# Module02.net
KiCad netlist of a schematic drawn in Altium Designer
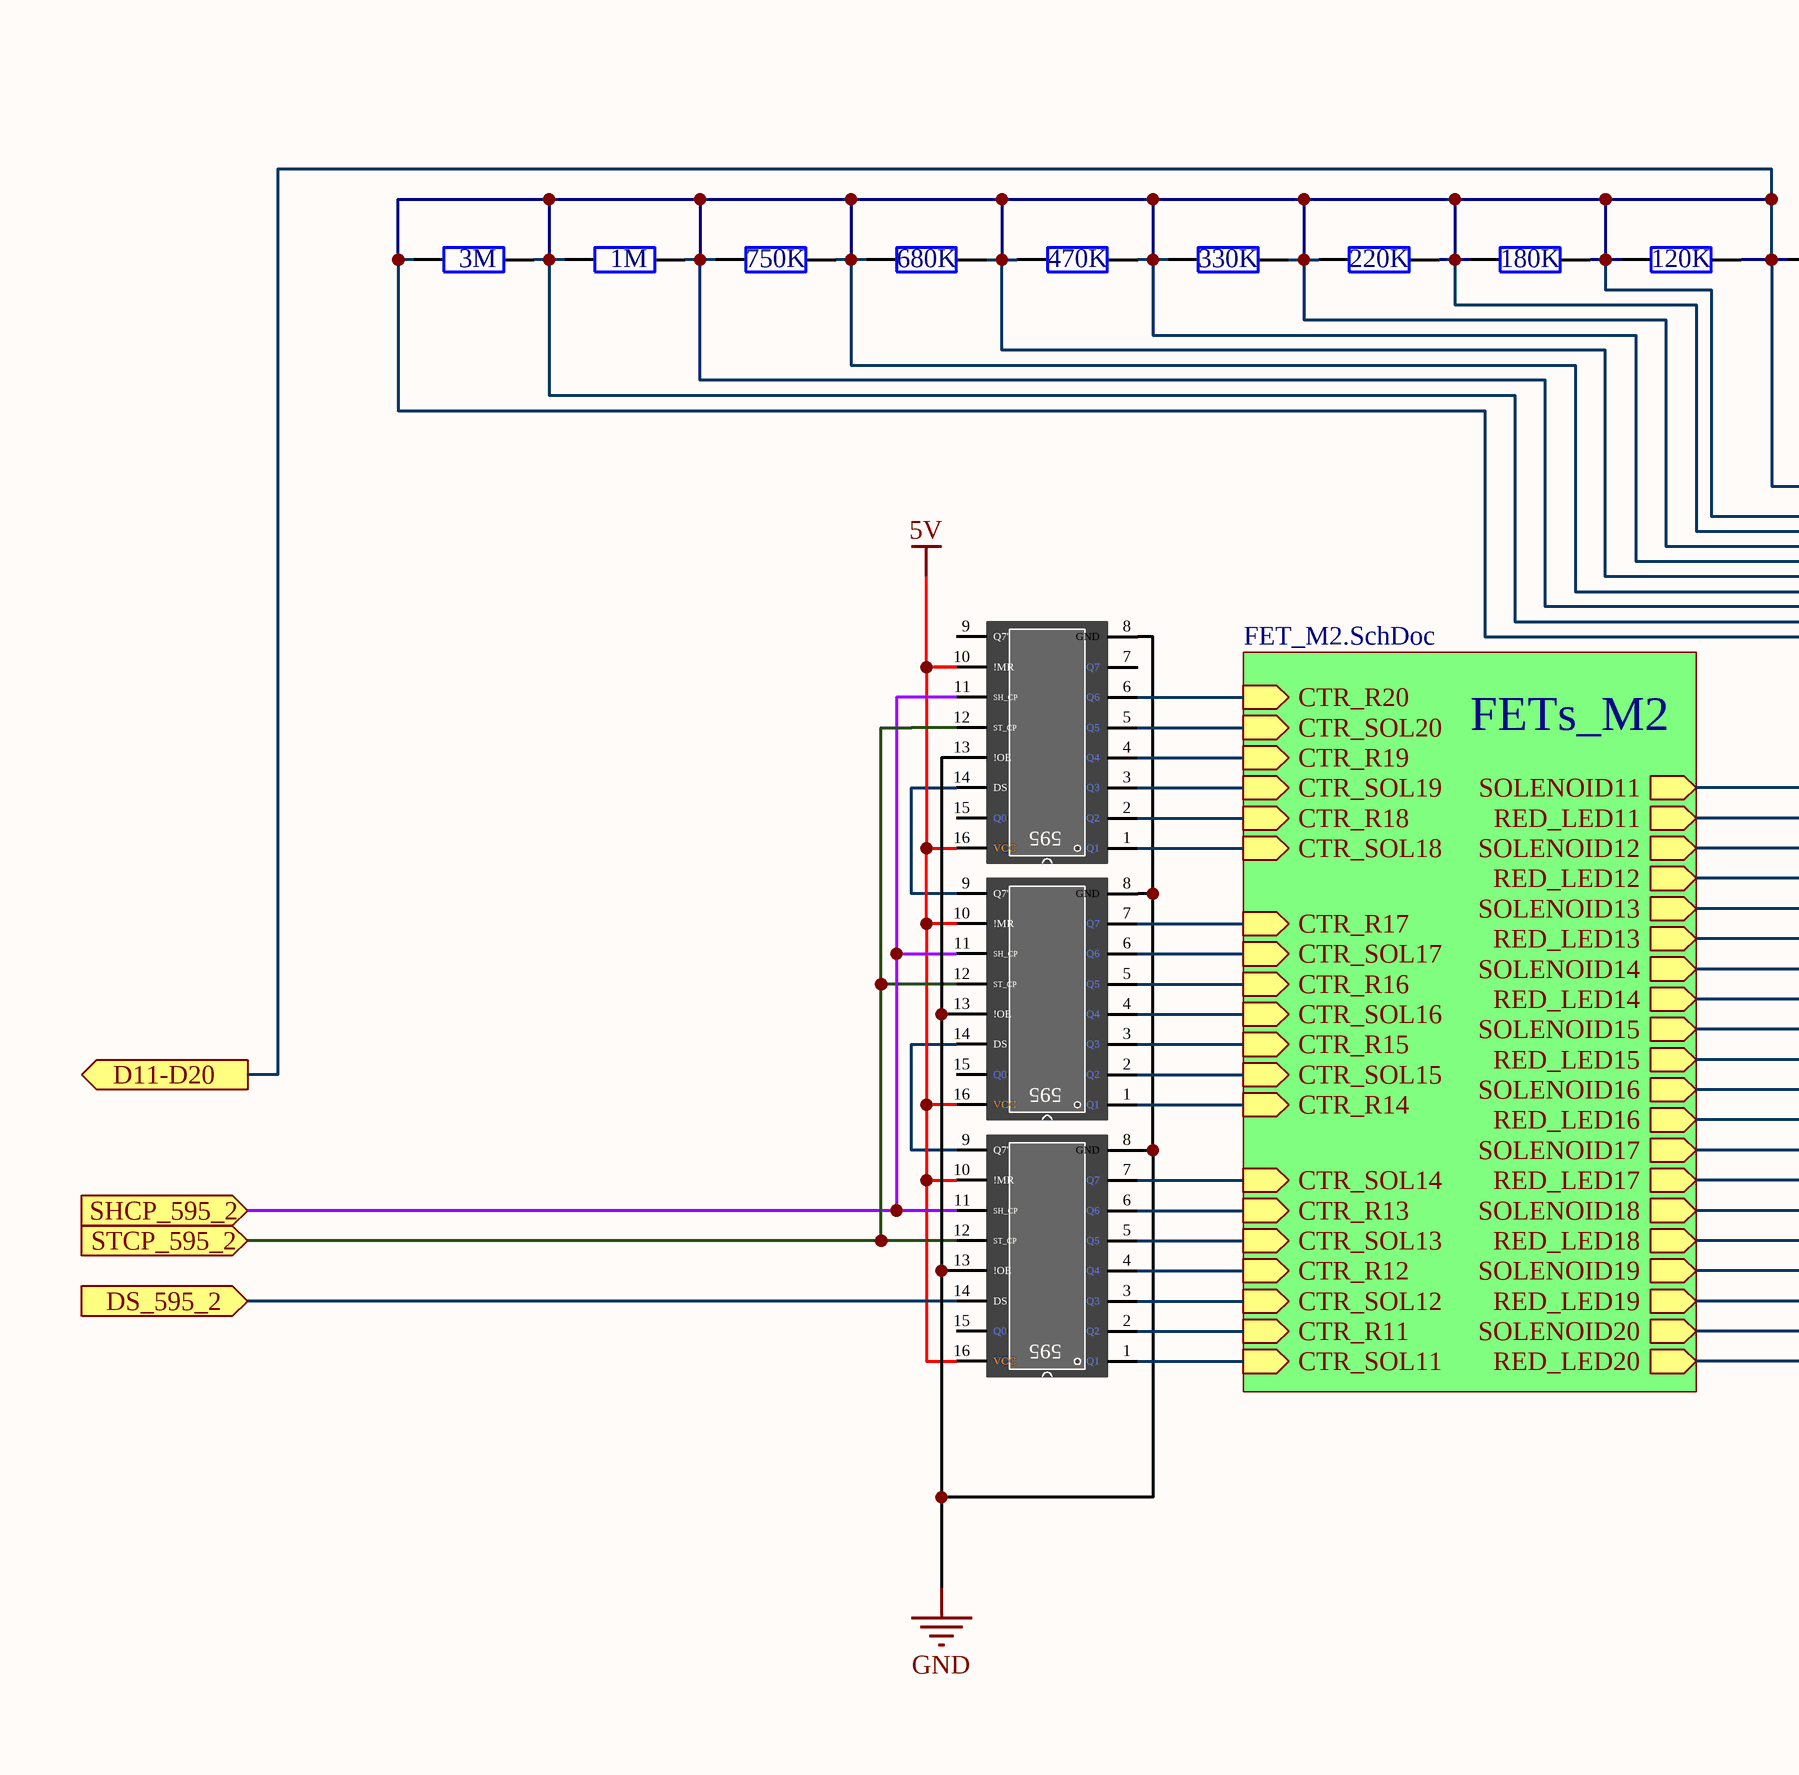
[diagram p0: Module02.SchDoc, left]
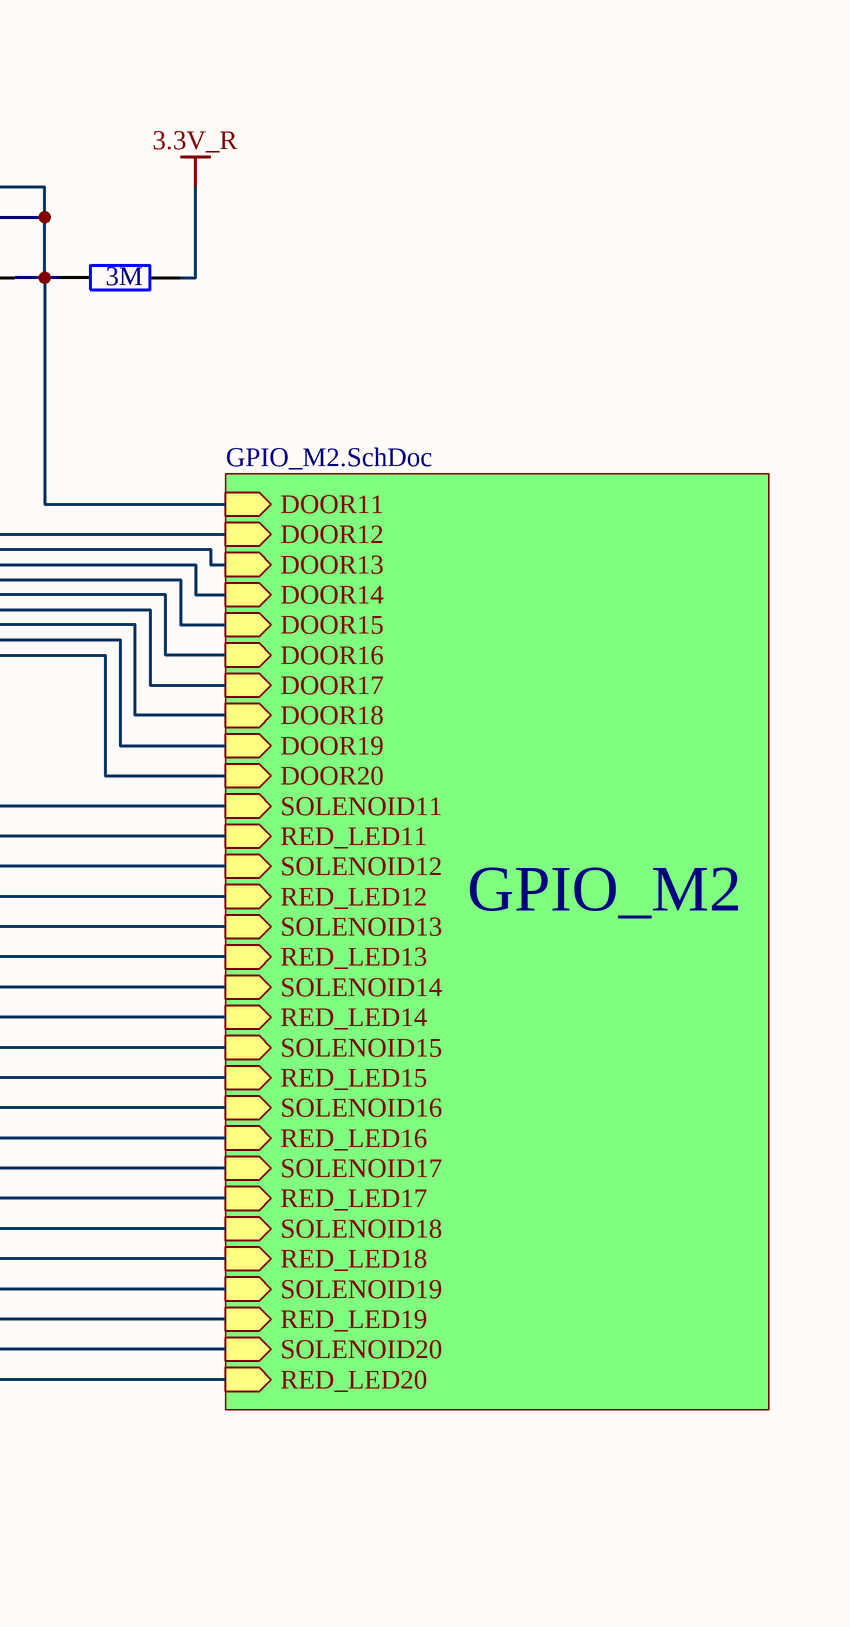
[diagram p1: Module02.SchDoc, right]

(export (version "E")
  (design (tool "Eeschema 10.0.6"))
  (components
    (comp (ref "4") (value "5#HC74595") (footprint "5#HC74595") (libsource (lib "Sch") (part "5#HC74595")))
    (comp (ref "5") (value "5#HC74595") (footprint "5#HC74595") (libsource (lib "Sch") (part "5#HC74595")))
    (comp (ref "6") (value "5#HC74595") (footprint "5#HC74595") (libsource (lib "Sch") (part "5#HC74595")))
    (comp (ref "R11")
      (value "3M")
      (footprint "AXIAL-0.4")
      (description "Resistor")
      (fields (field (name "PUBLISHER") "Altium Limited"))
      (libsource (lib "Miscellaneous Devices") (part "Res2"))
    )
    (comp (ref "R12")
      (value "1M")
      (footprint "AXIAL-0.4")
      (description "Resistor")
      (fields (field (name "PUBLISHER") "Altium Limited"))
      (libsource (lib "Miscellaneous Devices") (part "Res2"))
    )
    (comp (ref "R58")
      (value "750K")
      (footprint "AXIAL-0.4")
      (description "Resistor")
      (fields (field (name "PUBLISHER") "Altium Limited"))
      (libsource (lib "Miscellaneous Devices") (part "Res2"))
    )
    (comp (ref "R59")
      (value "680K")
      (footprint "AXIAL-0.4")
      (description "Resistor")
      (fields (field (name "PUBLISHER") "Altium Limited"))
      (libsource (lib "Miscellaneous Devices") (part "Res2"))
    )
    (comp (ref "R60")
      (value "470K")
      (footprint "AXIAL-0.4")
      (description "Resistor")
      (fields (field (name "PUBLISHER") "Altium Limited"))
      (libsource (lib "Miscellaneous Devices") (part "Res2"))
    )
    (comp (ref "R61")
      (value "330K")
      (footprint "AXIAL-0.4")
      (description "Resistor")
      (fields (field (name "PUBLISHER") "Altium Limited"))
      (libsource (lib "Miscellaneous Devices") (part "Res2"))
    )
    (comp (ref "R62")
      (value "220K")
      (footprint "AXIAL-0.4")
      (description "Resistor")
      (fields (field (name "PUBLISHER") "Altium Limited"))
      (libsource (lib "Miscellaneous Devices") (part "Res2"))
    )
    (comp (ref "R63")
      (value "180K")
      (footprint "AXIAL-0.4")
      (description "Resistor")
      (fields (field (name "PUBLISHER") "Altium Limited"))
      (libsource (lib "Miscellaneous Devices") (part "Res2"))
    )
    (comp (ref "R64")
      (value "120K")
      (footprint "AXIAL-0.4")
      (description "Resistor")
      (fields (field (name "PUBLISHER") "Altium Limited"))
      (libsource (lib "Miscellaneous Devices") (part "Res2"))
    )
    (comp (ref "R65")
      (value "3M")
      (footprint "AXIAL-0.4")
      (description "Resistor")
      (fields (field (name "PUBLISHER") "Altium Limited"))
      (libsource (lib "Miscellaneous Devices") (part "Res2"))
    )
  )
  (nets
    (net (code "1") (name "/CTR_R11") (class "Default")
      (node (ref "6") (pin "2") (pinfunction "Q2_2") (pintype "passive"))
    )
    (net (code "2") (name "/CTR_R12") (class "Default")
      (node (ref "6") (pin "4") (pinfunction "Q4_4") (pintype "passive"))
    )
    (net (code "3") (name "/CTR_R13") (class "Default")
      (node (ref "6") (pin "6") (pinfunction "Q6_6") (pintype "passive"))
    )
    (net (code "4") (name "/CTR_R14") (class "Default")
      (node (ref "5") (pin "1") (pinfunction "Q1_1") (pintype "passive"))
    )
    (net (code "5") (name "/CTR_R15") (class "Default")
      (node (ref "5") (pin "3") (pinfunction "Q3_3") (pintype "passive"))
    )
    (net (code "6") (name "/CTR_R16") (class "Default")
      (node (ref "5") (pin "5") (pinfunction "Q5_5") (pintype "passive"))
    )
    (net (code "7") (name "/CTR_R17") (class "Default")
      (node (ref "5") (pin "7") (pinfunction "Q7_7") (pintype "passive"))
    )
    (net (code "8") (name "/CTR_R18") (class "Default")
      (node (ref "4") (pin "2") (pinfunction "Q2_2") (pintype "passive"))
    )
    (net (code "9") (name "/CTR_R19") (class "Default")
      (node (ref "4") (pin "4") (pinfunction "Q4_4") (pintype "passive"))
    )
    (net (code "10") (name "/CTR_R20") (class "Default")
      (node (ref "4") (pin "6") (pinfunction "Q6_6") (pintype "passive"))
    )
    (net (code "11") (name "/CTR_SOL11") (class "Default")
      (node (ref "6") (pin "1") (pinfunction "Q1_1") (pintype "passive"))
    )
    (net (code "12") (name "/CTR_SOL12") (class "Default")
      (node (ref "6") (pin "3") (pinfunction "Q3_3") (pintype "passive"))
    )
    (net (code "13") (name "/CTR_SOL13") (class "Default")
      (node (ref "6") (pin "5") (pinfunction "Q5_5") (pintype "passive"))
    )
    (net (code "14") (name "/CTR_SOL14") (class "Default")
      (node (ref "6") (pin "7") (pinfunction "Q7_7") (pintype "passive"))
    )
    (net (code "15") (name "/CTR_SOL15") (class "Default")
      (node (ref "5") (pin "2") (pinfunction "Q2_2") (pintype "passive"))
    )
    (net (code "16") (name "/CTR_SOL16") (class "Default")
      (node (ref "5") (pin "4") (pinfunction "Q4_4") (pintype "passive"))
    )
    (net (code "17") (name "/CTR_SOL17") (class "Default")
      (node (ref "5") (pin "6") (pinfunction "Q6_6") (pintype "passive"))
    )
    (net (code "18") (name "/CTR_SOL18") (class "Default")
      (node (ref "4") (pin "1") (pinfunction "Q1_1") (pintype "passive"))
    )
    (net (code "19") (name "/CTR_SOL19") (class "Default")
      (node (ref "4") (pin "3") (pinfunction "Q3_3") (pintype "passive"))
    )
    (net (code "20") (name "/CTR_SOL20") (class "Default")
      (node (ref "4") (pin "5") (pinfunction "Q5_5") (pintype "passive"))
    )
    (net (code "21") (name "/D11-D20") (class "Default")
      (node (ref "R11") (pin "1") (pinfunction "1_1") (pintype "passive"))
      (node (ref "R11") (pin "2") (pinfunction "2_2") (pintype "passive"))
      (node (ref "R12") (pin "1") (pinfunction "1_1") (pintype "passive"))
      (node (ref "R12") (pin "2") (pinfunction "2_2") (pintype "passive"))
      (node (ref "R58") (pin "1") (pinfunction "1_1") (pintype "passive"))
      (node (ref "R58") (pin "2") (pinfunction "2_2") (pintype "passive"))
      (node (ref "R59") (pin "1") (pinfunction "1_1") (pintype "passive"))
      (node (ref "R59") (pin "2") (pinfunction "2_2") (pintype "passive"))
      (node (ref "R60") (pin "1") (pinfunction "1_1") (pintype "passive"))
      (node (ref "R60") (pin "2") (pinfunction "2_2") (pintype "passive"))
      (node (ref "R61") (pin "1") (pinfunction "1_1") (pintype "passive"))
      (node (ref "R61") (pin "2") (pinfunction "2_2") (pintype "passive"))
      (node (ref "R62") (pin "1") (pinfunction "1_1") (pintype "passive"))
      (node (ref "R62") (pin "2") (pinfunction "2_2") (pintype "passive"))
      (node (ref "R63") (pin "1") (pinfunction "1_1") (pintype "passive"))
      (node (ref "R63") (pin "2") (pinfunction "2_2") (pintype "passive"))
      (node (ref "R64") (pin "1") (pinfunction "1_1") (pintype "passive"))
      (node (ref "R64") (pin "2") (pinfunction "2_2") (pintype "passive"))
      (node (ref "R65") (pin "2") (pinfunction "2_2") (pintype "passive"))
    )
    (net (code "22") (name "/DS_595_2") (class "Default")
      (node (ref "6") (pin "14") (pinfunction "DS_14") (pintype "passive"))
    )
    (net (code "33") (name "/SHCP_595_2") (class "Default")
      (node (ref "4") (pin "11") (pinfunction "SH_CP_11") (pintype "passive"))
      (node (ref "5") (pin "11") (pinfunction "SH_CP_11") (pintype "passive"))
      (node (ref "6") (pin "11") (pinfunction "SH_CP_11") (pintype "passive"))
    )
    (net (code "44") (name "/STCP_595_2") (class "Default")
      (node (ref "4") (pin "12") (pinfunction "ST_CP_12") (pintype "passive"))
      (node (ref "5") (pin "12") (pinfunction "ST_CP_12") (pintype "passive"))
      (node (ref "6") (pin "12") (pinfunction "ST_CP_12") (pintype "passive"))
    )
    (net (code "45") (name "3.3V_R") (class "Default")
      (node (ref "R65") (pin "1") (pinfunction "1_1") (pintype "passive"))
    )
    (net (code "46") (name "5V") (class "Default")
      (node (ref "4") (pin "10") (pinfunction "!MR_10") (pintype "passive"))
      (node (ref "4") (pin "16") (pinfunction "VCC_16") (pintype "passive"))
      (node (ref "5") (pin "10") (pinfunction "!MR_10") (pintype "passive"))
      (node (ref "5") (pin "16") (pinfunction "VCC_16") (pintype "passive"))
      (node (ref "6") (pin "10") (pinfunction "!MR_10") (pintype "passive"))
      (node (ref "6") (pin "16") (pinfunction "VCC_16") (pintype "passive"))
    )
    (net (code "47") (name "GND") (class "Default")
      (node (ref "4") (pin "13") (pinfunction "!OE_13") (pintype "passive"))
      (node (ref "4") (pin "8") (pinfunction "GND_8") (pintype "passive"))
      (node (ref "5") (pin "13") (pinfunction "!OE_13") (pintype "passive"))
      (node (ref "5") (pin "8") (pinfunction "GND_8") (pintype "passive"))
      (node (ref "6") (pin "13") (pinfunction "!OE_13") (pintype "passive"))
      (node (ref "6") (pin "8") (pinfunction "GND_8") (pintype "passive"))
    )
    (net (code "48") (name "Net-(4-DS)") (class "Default")
      (node (ref "4") (pin "14") (pinfunction "DS_14") (pintype "passive"))
      (node (ref "5") (pin "9") (pinfunction "Q7'_9") (pintype "passive"))
    )
    (net (code "49") (name "Net-(5-DS)") (class "Default")
      (node (ref "5") (pin "14") (pinfunction "DS_14") (pintype "passive"))
      (node (ref "6") (pin "9") (pinfunction "Q7'_9") (pintype "passive"))
    )
    (net (code "50") (name "unconnected-(4-Q0-Pad15)") (class "Default")
      (node (ref "4") (pin "15") (pinfunction "Q0_15") (pintype "passive"))
    )
    (net (code "51") (name "unconnected-(4-Q7'-Pad9)") (class "Default")
      (node (ref "4") (pin "9") (pinfunction "Q7'_9") (pintype "passive"))
    )
    (net (code "52") (name "unconnected-(4-Q7-Pad7)") (class "Default")
      (node (ref "4") (pin "7") (pinfunction "Q7_7") (pintype "passive"))
    )
    (net (code "53") (name "unconnected-(5-Q0-Pad15)") (class "Default")
      (node (ref "5") (pin "15") (pinfunction "Q0_15") (pintype "passive"))
    )
    (net (code "54") (name "unconnected-(6-Q0-Pad15)") (class "Default")
      (node (ref "6") (pin "15") (pinfunction "Q0_15") (pintype "passive"))
    )
  )
)
